# No_3.net
KiCad netlist of a schematic drawn in Altium Designer
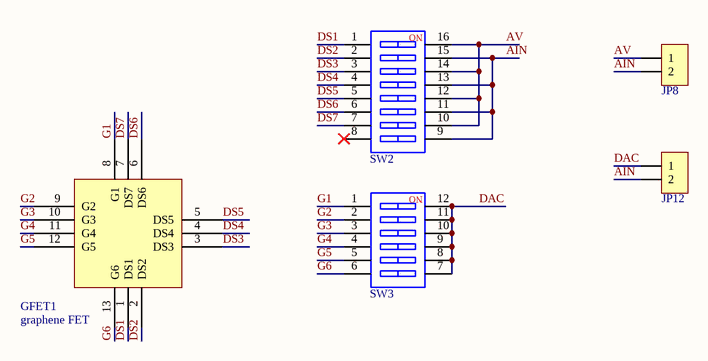
[diagram p0: No.3 跳线板.SchDoc]

(export (version "E")
  (design (tool "Eeschema 10.0.6"))
  (components
    (comp (ref "GFET1")
      (value "graphene FET")
      (footprint "graphene FET")
      (libsource (lib "Schlib1") (part "graphene FET"))
    )
    (comp (ref "JP8")
      (value "HDR-1X2")
      (footprint "XH2.54-WI-2P")
      (description "2P接插件")
      (libsource (lib "4.5   - 接插件-脚距2.54") (part "Header 2"))
    )
    (comp (ref "JP12")
      (value "HDR-1X2")
      (footprint "XH2.54-WI-2P")
      (description "2P接插件")
      (libsource (lib "4.5   - 接插件-脚距2.54") (part "Header 2"))
    )
    (comp (ref "SW2")
      (value "CSW-8P")
      (footprint "CSW1.27 SMD-8P")
      (description "8路编码开关")
      (libsource (lib "5.1   - 按键-开关") (part "CSW-8P"))
    )
    (comp (ref "SW3")
      (value "CSW-6P")
      (footprint "CSW1.27 SMD-6P")
      (description "6路编码开关")
      (libsource (lib "5.1   - 按键-开关") (part "CSW-6P"))
    )
  )
  (nets
    (net (code "1") (name "/AIN") (class "Default")
      (node (ref "JP12") (pin "2") (pinfunction "2_2") (pintype "passive"))
      (node (ref "JP8") (pin "2") (pinfunction "2_2") (pintype "passive"))
      (node (ref "SW2") (pin "11") (pinfunction "11_11") (pintype "passive"))
      (node (ref "SW2") (pin "13") (pinfunction "13_13") (pintype "passive"))
      (node (ref "SW2") (pin "15") (pinfunction "15_15") (pintype "passive"))
      (node (ref "SW2") (pin "9") (pinfunction "9_9") (pintype "passive"))
    )
    (net (code "2") (name "/AV") (class "Default")
      (node (ref "JP8") (pin "1") (pinfunction "1_1") (pintype "passive"))
      (node (ref "SW2") (pin "10") (pinfunction "10_10") (pintype "passive"))
      (node (ref "SW2") (pin "12") (pinfunction "12_12") (pintype "passive"))
      (node (ref "SW2") (pin "14") (pinfunction "14_14") (pintype "passive"))
      (node (ref "SW2") (pin "16") (pinfunction "16_16") (pintype "passive"))
    )
    (net (code "3") (name "/DAC") (class "Default")
      (node (ref "JP12") (pin "1") (pinfunction "1_1") (pintype "passive"))
      (node (ref "SW3") (pin "10") (pinfunction "10_10") (pintype "passive"))
      (node (ref "SW3") (pin "11") (pinfunction "11_11") (pintype "passive"))
      (node (ref "SW3") (pin "12") (pinfunction "12_12") (pintype "passive"))
      (node (ref "SW3") (pin "7") (pinfunction "7_7") (pintype "passive"))
      (node (ref "SW3") (pin "8") (pinfunction "8_8") (pintype "passive"))
      (node (ref "SW3") (pin "9") (pinfunction "9_9") (pintype "passive"))
    )
    (net (code "4") (name "/DS1") (class "Default")
      (node (ref "GFET1") (pin "1") (pinfunction "DS1_1") (pintype "passive"))
      (node (ref "SW2") (pin "1") (pinfunction "1_1") (pintype "passive"))
    )
    (net (code "5") (name "/DS2") (class "Default")
      (node (ref "GFET1") (pin "2") (pinfunction "DS2_2") (pintype "passive"))
      (node (ref "SW2") (pin "2") (pinfunction "2_2") (pintype "passive"))
    )
    (net (code "6") (name "/DS3") (class "Default")
      (node (ref "GFET1") (pin "3") (pinfunction "DS3_3") (pintype "passive"))
      (node (ref "SW2") (pin "3") (pinfunction "3_3") (pintype "passive"))
    )
    (net (code "7") (name "/DS4") (class "Default")
      (node (ref "GFET1") (pin "4") (pinfunction "DS4_4") (pintype "passive"))
      (node (ref "SW2") (pin "4") (pinfunction "4_4") (pintype "passive"))
    )
    (net (code "8") (name "/DS5") (class "Default")
      (node (ref "GFET1") (pin "5") (pinfunction "DS5_5") (pintype "passive"))
      (node (ref "SW2") (pin "5") (pinfunction "5_5") (pintype "passive"))
    )
    (net (code "9") (name "/DS6") (class "Default")
      (node (ref "GFET1") (pin "6") (pinfunction "DS6_6") (pintype "passive"))
      (node (ref "SW2") (pin "6") (pinfunction "6_6") (pintype "passive"))
    )
    (net (code "10") (name "/DS7") (class "Default")
      (node (ref "GFET1") (pin "7") (pinfunction "DS7_7") (pintype "passive"))
      (node (ref "SW2") (pin "7") (pinfunction "7_7") (pintype "passive"))
    )
    (net (code "11") (name "/G1") (class "Default")
      (node (ref "GFET1") (pin "8") (pinfunction "G1_8") (pintype "passive"))
      (node (ref "SW3") (pin "1") (pinfunction "1_1") (pintype "passive"))
    )
    (net (code "12") (name "/G2") (class "Default")
      (node (ref "GFET1") (pin "9") (pinfunction "G2_9") (pintype "passive"))
      (node (ref "SW3") (pin "2") (pinfunction "2_2") (pintype "passive"))
    )
    (net (code "13") (name "/G3") (class "Default")
      (node (ref "GFET1") (pin "10") (pinfunction "G3_10") (pintype "passive"))
      (node (ref "SW3") (pin "3") (pinfunction "3_3") (pintype "passive"))
    )
    (net (code "14") (name "/G4") (class "Default")
      (node (ref "GFET1") (pin "11") (pinfunction "G4_11") (pintype "passive"))
      (node (ref "SW3") (pin "4") (pinfunction "4_4") (pintype "passive"))
    )
    (net (code "15") (name "/G5") (class "Default")
      (node (ref "GFET1") (pin "12") (pinfunction "G5_12") (pintype "passive"))
      (node (ref "SW3") (pin "5") (pinfunction "5_5") (pintype "passive"))
    )
    (net (code "16") (name "/G6") (class "Default")
      (node (ref "GFET1") (pin "13") (pinfunction "G6_13") (pintype "passive"))
      (node (ref "SW3") (pin "6") (pinfunction "6_6") (pintype "passive"))
    )
    (net (code "17") (name "unconnected-(SW2-Pad8)") (class "Default")
      (node (ref "SW2") (pin "8") (pinfunction "8_8") (pintype "passive+no_connect"))
    )
  )
)
